# MotorControl.net
KiCad netlist of a schematic drawn in EAGLE
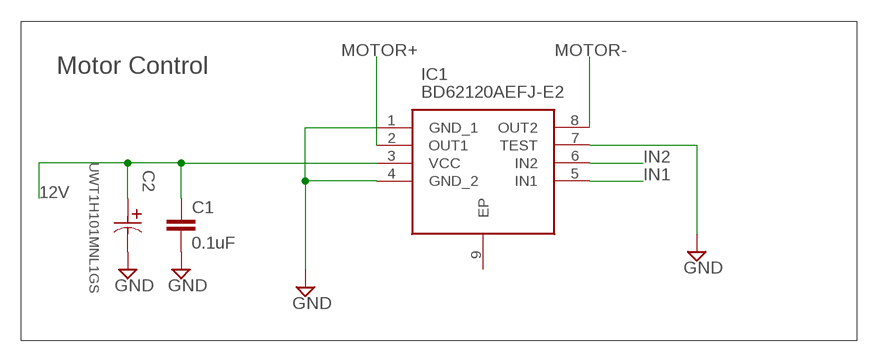
[diagram p0: schematic, sheet 1]

(export (version "E")
  (design (tool "Eeschema 10.0.6"))
  (components
    (comp (ref "C1")
      (value "0.1uF")
      (footprint "eagle-import:C0402")
      (libsource (lib "eagle-import") (part "C-EUC0402"))
    )
    (comp (ref "C2")
      (value "UWT1H101MNL1GS")
      (footprint "eagle-import:PCAP_8X10-ELECT")
      (libsource (lib "eagle-import") (part "UWT1H101MNL1GS"))
    )
    (comp (ref "IC1")
      (value "BD62120AEFJ-E2")
      (footprint "eagle-import:SOIC127P600X100-9N")
      (fields (field (name "MOUSER_PART_NUMBER") "755-BD62120AEFJ-E2"))
      (libsource (lib "eagle-import") (part "BD62120AEFJ-E2"))
    )
  )
  (nets
    (net (code "1") (name "/12V") (class "Default")
      (node (ref "C1") (pin "1") (pinfunction "1_1") (pintype "passive"))
      (node (ref "C2") (pin "1") (pinfunction "1_1") (pintype "passive"))
      (node (ref "IC1") (pin "3") (pinfunction "VCC_3") (pintype "bidirectional"))
    )
    (net (code "2") (name "/IN1") (class "Default")
      (node (ref "IC1") (pin "5") (pinfunction "IN1_5") (pintype "bidirectional"))
    )
    (net (code "3") (name "/IN2") (class "Default")
      (node (ref "IC1") (pin "6") (pinfunction "IN2_6") (pintype "bidirectional"))
    )
    (net (code "4") (name "/MOTOR+") (class "Default")
      (node (ref "IC1") (pin "2") (pinfunction "OUT1_2") (pintype "bidirectional"))
    )
    (net (code "5") (name "/MOTOR-") (class "Default")
      (node (ref "IC1") (pin "8") (pinfunction "OUT2_8") (pintype "bidirectional"))
    )
    (net (code "6") (name "GND") (class "Default")
      (node (ref "C1") (pin "2") (pinfunction "2_2") (pintype "passive"))
      (node (ref "C2") (pin "2") (pinfunction "2_2") (pintype "passive"))
      (node (ref "IC1") (pin "1") (pinfunction "GND_1_1") (pintype "bidirectional"))
      (node (ref "IC1") (pin "4") (pinfunction "GND_2_4") (pintype "bidirectional"))
      (node (ref "IC1") (pin "7") (pinfunction "TEST_7") (pintype "bidirectional"))
    )
    (net (code "7") (name "unconnected-(IC1-EP-Pad9)") (class "Default")
      (node (ref "IC1") (pin "9") (pinfunction "EP_9") (pintype "bidirectional"))
    )
  )
)
